# Sheet2.net
KiCad netlist of a schematic drawn in Altium Designer
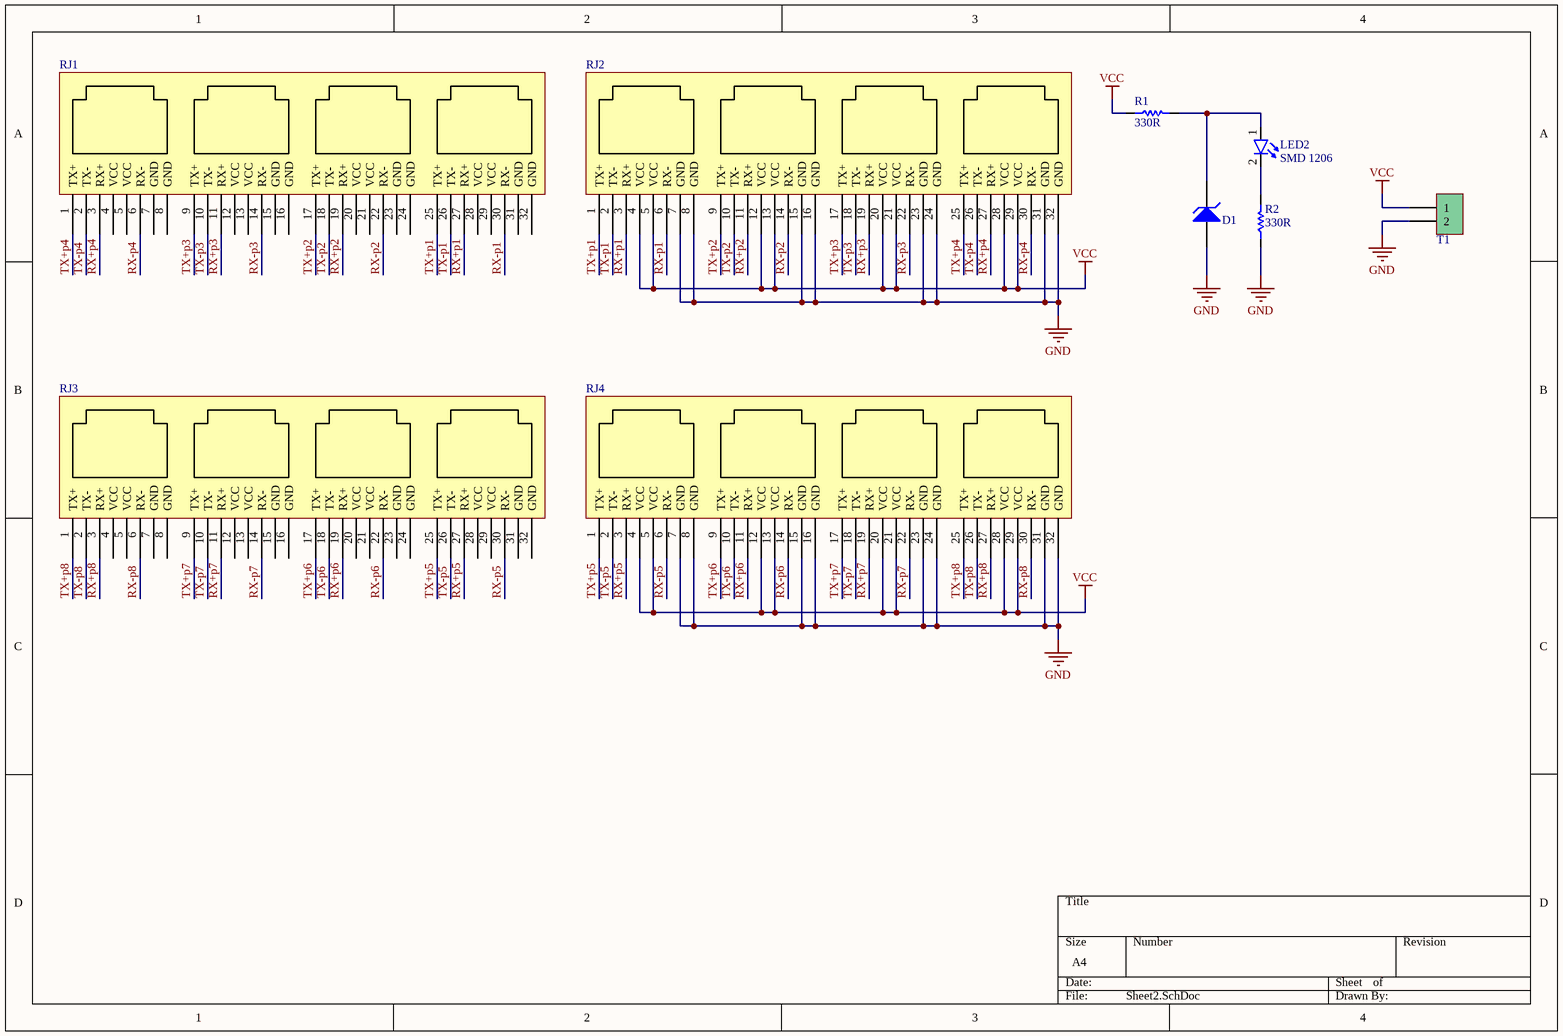
[diagram p0: Sheet2.SchDoc]

(export (version "E")
  (design (tool "Eeschema 10.0.6"))
  (components
    (comp (ref "D1")
      (value "Diode Zener")
      (footprint "Diode 1W")
      (description "Zener Diode")
      (fields (field (name "VOLTAGE") "12V") (field (name "DESIGNER") "Saeid Jorablo"))
      (libsource (lib "Electrovolt Lib") (part "Diode Zener"))
    )
    (comp (ref "LED2")
      (value "Red")
      (footprint "LED-5mm")
      (description "LED")
      (fields (field (name "SIZE") "SMD 1206") (field (name "DESIGNER") "Saeid Jorablo"))
      (libsource (lib "Electrovolt Lib") (part "LED"))
    )
    (comp (ref "R1")
      (value "330R")
      (footprint "RES 1206 (3216X08L)")
      (description "Resistor")
      (fields (field (name "TOLERANCE") "5%") (field (name "POWER") "1/8 W"))
      (libsource (lib "Electrovolt Lib") (part "Resistor"))
    )
    (comp (ref "R2")
      (value "330R")
      (footprint "RES 1206 (3216X08L)")
      (description "Resistor")
      (fields (field (name "TOLERANCE") "5%") (field (name "POWER") "1/8 W"))
      (libsource (lib "Electrovolt Lib") (part "Resistor"))
    )
    (comp (ref "RJ1") (value "~") (footprint "rj45-w57-4") (libsource (lib "Schlib1") (part "RJ45-w57-4")))
    (comp (ref "RJ2") (value "~") (footprint "rj45-w57-4") (libsource (lib "Schlib1") (part "RJ45-w57-4")))
    (comp (ref "RJ3") (value "~") (footprint "rj45-w57-4") (libsource (lib "Schlib1") (part "RJ45-w57-4")))
    (comp (ref "RJ4") (value "~") (footprint "rj45-w57-4") (libsource (lib "Schlib1") (part "RJ45-w57-4")))
    (comp (ref "T1")
      (value "Phoenix terminal")
      (footprint "phoenix terminal 2")
      (description "Terminal 2 Pin")
      (fields (field (name "DESIGNER") "Seyed Mohsen Ghasemain") (field (name "E-MAIL") "picpars@gmail.com"))
      (libsource (lib "usefully_Library") (part "Phoenix terminal 2"))
    )
  )
  (nets
    (net (code "1") (name "/RX+p1") (class "Default")
      (node (ref "RJ1") (pin "27") (pinfunction "RX+_27") (pintype "passive"))
      (node (ref "RJ2") (pin "3") (pinfunction "RX+_3") (pintype "passive"))
    )
    (net (code "2") (name "/RX+p2") (class "Default")
      (node (ref "RJ1") (pin "19") (pinfunction "RX+_19") (pintype "passive"))
      (node (ref "RJ2") (pin "11") (pinfunction "RX+_11") (pintype "passive"))
    )
    (net (code "3") (name "/RX+p3") (class "Default")
      (node (ref "RJ1") (pin "11") (pinfunction "RX+_11") (pintype "passive"))
      (node (ref "RJ2") (pin "19") (pinfunction "RX+_19") (pintype "passive"))
    )
    (net (code "4") (name "/RX+p4") (class "Default")
      (node (ref "RJ1") (pin "3") (pinfunction "RX+_3") (pintype "passive"))
      (node (ref "RJ2") (pin "27") (pinfunction "RX+_27") (pintype "passive"))
    )
    (net (code "5") (name "/RX+p5") (class "Default")
      (node (ref "RJ3") (pin "27") (pinfunction "RX+_27") (pintype "passive"))
      (node (ref "RJ4") (pin "3") (pinfunction "RX+_3") (pintype "passive"))
    )
    (net (code "6") (name "/RX+p6") (class "Default")
      (node (ref "RJ3") (pin "19") (pinfunction "RX+_19") (pintype "passive"))
      (node (ref "RJ4") (pin "11") (pinfunction "RX+_11") (pintype "passive"))
    )
    (net (code "7") (name "/RX+p7") (class "Default")
      (node (ref "RJ3") (pin "11") (pinfunction "RX+_11") (pintype "passive"))
      (node (ref "RJ4") (pin "19") (pinfunction "RX+_19") (pintype "passive"))
    )
    (net (code "8") (name "/RX+p8") (class "Default")
      (node (ref "RJ3") (pin "3") (pinfunction "RX+_3") (pintype "passive"))
      (node (ref "RJ4") (pin "27") (pinfunction "RX+_27") (pintype "passive"))
    )
    (net (code "9") (name "/RX-p1") (class "Default")
      (node (ref "RJ1") (pin "30") (pinfunction "RX-_30") (pintype "passive"))
      (node (ref "RJ2") (pin "6") (pinfunction "RX-_6") (pintype "passive"))
    )
    (net (code "10") (name "/RX-p2") (class "Default")
      (node (ref "RJ1") (pin "22") (pinfunction "RX-_22") (pintype "passive"))
      (node (ref "RJ2") (pin "14") (pinfunction "RX-_14") (pintype "passive"))
    )
    (net (code "11") (name "/RX-p3") (class "Default")
      (node (ref "RJ1") (pin "14") (pinfunction "RX-_14") (pintype "passive"))
      (node (ref "RJ2") (pin "22") (pinfunction "RX-_22") (pintype "passive"))
    )
    (net (code "12") (name "/RX-p4") (class "Default")
      (node (ref "RJ1") (pin "6") (pinfunction "RX-_6") (pintype "passive"))
      (node (ref "RJ2") (pin "30") (pinfunction "RX-_30") (pintype "passive"))
    )
    (net (code "13") (name "/RX-p5") (class "Default")
      (node (ref "RJ3") (pin "30") (pinfunction "RX-_30") (pintype "passive"))
      (node (ref "RJ4") (pin "6") (pinfunction "RX-_6") (pintype "passive"))
    )
    (net (code "14") (name "/RX-p6") (class "Default")
      (node (ref "RJ3") (pin "22") (pinfunction "RX-_22") (pintype "passive"))
      (node (ref "RJ4") (pin "14") (pinfunction "RX-_14") (pintype "passive"))
    )
    (net (code "15") (name "/RX-p7") (class "Default")
      (node (ref "RJ3") (pin "14") (pinfunction "RX-_14") (pintype "passive"))
      (node (ref "RJ4") (pin "22") (pinfunction "RX-_22") (pintype "passive"))
    )
    (net (code "16") (name "/RX-p8") (class "Default")
      (node (ref "RJ3") (pin "6") (pinfunction "RX-_6") (pintype "passive"))
      (node (ref "RJ4") (pin "30") (pinfunction "RX-_30") (pintype "passive"))
    )
    (net (code "17") (name "/TX+p1") (class "Default")
      (node (ref "RJ1") (pin "25") (pinfunction "TX+_25") (pintype "passive"))
      (node (ref "RJ2") (pin "1") (pinfunction "TX+_1") (pintype "passive"))
    )
    (net (code "18") (name "/TX+p2") (class "Default")
      (node (ref "RJ1") (pin "17") (pinfunction "TX+_17") (pintype "passive"))
      (node (ref "RJ2") (pin "9") (pinfunction "TX+_9") (pintype "passive"))
    )
    (net (code "19") (name "/TX+p3") (class "Default")
      (node (ref "RJ1") (pin "9") (pinfunction "TX+_9") (pintype "passive"))
      (node (ref "RJ2") (pin "17") (pinfunction "TX+_17") (pintype "passive"))
    )
    (net (code "20") (name "/TX+p4") (class "Default")
      (node (ref "RJ1") (pin "1") (pinfunction "TX+_1") (pintype "passive"))
      (node (ref "RJ2") (pin "25") (pinfunction "TX+_25") (pintype "passive"))
    )
    (net (code "21") (name "/TX+p5") (class "Default")
      (node (ref "RJ3") (pin "25") (pinfunction "TX+_25") (pintype "passive"))
      (node (ref "RJ4") (pin "1") (pinfunction "TX+_1") (pintype "passive"))
    )
    (net (code "22") (name "/TX+p6") (class "Default")
      (node (ref "RJ3") (pin "17") (pinfunction "TX+_17") (pintype "passive"))
      (node (ref "RJ4") (pin "9") (pinfunction "TX+_9") (pintype "passive"))
    )
    (net (code "23") (name "/TX+p7") (class "Default")
      (node (ref "RJ3") (pin "9") (pinfunction "TX+_9") (pintype "passive"))
      (node (ref "RJ4") (pin "17") (pinfunction "TX+_17") (pintype "passive"))
    )
    (net (code "24") (name "/TX+p8") (class "Default")
      (node (ref "RJ3") (pin "1") (pinfunction "TX+_1") (pintype "passive"))
      (node (ref "RJ4") (pin "25") (pinfunction "TX+_25") (pintype "passive"))
    )
    (net (code "25") (name "/TX-p1") (class "Default")
      (node (ref "RJ1") (pin "26") (pinfunction "TX-_26") (pintype "passive"))
      (node (ref "RJ2") (pin "2") (pinfunction "TX-_2") (pintype "passive"))
    )
    (net (code "26") (name "/TX-p2") (class "Default")
      (node (ref "RJ1") (pin "18") (pinfunction "TX-_18") (pintype "passive"))
      (node (ref "RJ2") (pin "10") (pinfunction "TX-_10") (pintype "passive"))
    )
    (net (code "27") (name "/TX-p3") (class "Default")
      (node (ref "RJ1") (pin "10") (pinfunction "TX-_10") (pintype "passive"))
      (node (ref "RJ2") (pin "18") (pinfunction "TX-_18") (pintype "passive"))
    )
    (net (code "28") (name "/TX-p4") (class "Default")
      (node (ref "RJ1") (pin "2") (pinfunction "TX-_2") (pintype "passive"))
      (node (ref "RJ2") (pin "26") (pinfunction "TX-_26") (pintype "passive"))
    )
    (net (code "29") (name "/TX-p5") (class "Default")
      (node (ref "RJ3") (pin "26") (pinfunction "TX-_26") (pintype "passive"))
      (node (ref "RJ4") (pin "2") (pinfunction "TX-_2") (pintype "passive"))
    )
    (net (code "30") (name "/TX-p6") (class "Default")
      (node (ref "RJ3") (pin "18") (pinfunction "TX-_18") (pintype "passive"))
      (node (ref "RJ4") (pin "10") (pinfunction "TX-_10") (pintype "passive"))
    )
    (net (code "31") (name "/TX-p7") (class "Default")
      (node (ref "RJ3") (pin "10") (pinfunction "TX-_10") (pintype "passive"))
      (node (ref "RJ4") (pin "18") (pinfunction "TX-_18") (pintype "passive"))
    )
    (net (code "32") (name "/TX-p8") (class "Default")
      (node (ref "RJ3") (pin "2") (pinfunction "TX-_2") (pintype "passive"))
      (node (ref "RJ4") (pin "26") (pinfunction "TX-_26") (pintype "passive"))
    )
    (net (code "33") (name "GND") (class "Default")
      (node (ref "D1") (pin "1") (pinfunction "A_1") (pintype "passive"))
      (node (ref "R2") (pin "1") (pinfunction "1_1") (pintype "passive"))
      (node (ref "RJ2") (pin "15") (pinfunction "GND_15") (pintype "passive"))
      (node (ref "RJ2") (pin "16") (pinfunction "GND_16") (pintype "passive"))
      (node (ref "RJ2") (pin "23") (pinfunction "GND_23") (pintype "passive"))
      (node (ref "RJ2") (pin "24") (pinfunction "GND_24") (pintype "passive"))
      (node (ref "RJ2") (pin "31") (pinfunction "GND_31") (pintype "passive"))
      (node (ref "RJ2") (pin "32") (pinfunction "GND_32") (pintype "passive"))
      (node (ref "RJ2") (pin "7") (pinfunction "GND_7") (pintype "passive"))
      (node (ref "RJ2") (pin "8") (pinfunction "GND_8") (pintype "passive"))
      (node (ref "RJ4") (pin "15") (pinfunction "GND_15") (pintype "passive"))
      (node (ref "RJ4") (pin "16") (pinfunction "GND_16") (pintype "passive"))
      (node (ref "RJ4") (pin "23") (pinfunction "GND_23") (pintype "passive"))
      (node (ref "RJ4") (pin "24") (pinfunction "GND_24") (pintype "passive"))
      (node (ref "RJ4") (pin "31") (pinfunction "GND_31") (pintype "passive"))
      (node (ref "RJ4") (pin "32") (pinfunction "GND_32") (pintype "passive"))
      (node (ref "RJ4") (pin "7") (pinfunction "GND_7") (pintype "passive"))
      (node (ref "RJ4") (pin "8") (pinfunction "GND_8") (pintype "passive"))
      (node (ref "T1") (pin "2") (pinfunction "2_2") (pintype "passive"))
    )
    (net (code "34") (name "Net-(D1-K)") (class "Default")
      (node (ref "D1") (pin "2") (pinfunction "K_2") (pintype "passive"))
      (node (ref "LED2") (pin "1") (pinfunction "A_1") (pintype "passive"))
      (node (ref "R1") (pin "2") (pinfunction "2_2") (pintype "passive"))
    )
    (net (code "35") (name "Net-(LED2-K)") (class "Default")
      (node (ref "LED2") (pin "2") (pinfunction "K_2") (pintype "passive"))
      (node (ref "R2") (pin "2") (pinfunction "2_2") (pintype "passive"))
    )
    (net (code "36") (name "VCC") (class "Default")
      (node (ref "R1") (pin "1") (pinfunction "1_1") (pintype "passive"))
      (node (ref "RJ2") (pin "12") (pinfunction "VCC_12") (pintype "passive"))
      (node (ref "RJ2") (pin "13") (pinfunction "VCC_13") (pintype "passive"))
      (node (ref "RJ2") (pin "20") (pinfunction "VCC_20") (pintype "passive"))
      (node (ref "RJ2") (pin "21") (pinfunction "VCC_21") (pintype "passive"))
      (node (ref "RJ2") (pin "28") (pinfunction "VCC_28") (pintype "passive"))
      (node (ref "RJ2") (pin "29") (pinfunction "VCC_29") (pintype "passive"))
      (node (ref "RJ2") (pin "4") (pinfunction "VCC_4") (pintype "passive"))
      (node (ref "RJ2") (pin "5") (pinfunction "VCC_5") (pintype "passive"))
      (node (ref "RJ4") (pin "12") (pinfunction "VCC_12") (pintype "passive"))
      (node (ref "RJ4") (pin "13") (pinfunction "VCC_13") (pintype "passive"))
      (node (ref "RJ4") (pin "20") (pinfunction "VCC_20") (pintype "passive"))
      (node (ref "RJ4") (pin "21") (pinfunction "VCC_21") (pintype "passive"))
      (node (ref "RJ4") (pin "28") (pinfunction "VCC_28") (pintype "passive"))
      (node (ref "RJ4") (pin "29") (pinfunction "VCC_29") (pintype "passive"))
      (node (ref "RJ4") (pin "4") (pinfunction "VCC_4") (pintype "passive"))
      (node (ref "RJ4") (pin "5") (pinfunction "VCC_5") (pintype "passive"))
      (node (ref "T1") (pin "1") (pinfunction "1_1") (pintype "passive"))
    )
    (net (code "37") (name "unconnected-(RJ1-GND-Pad7)") (class "Default")
      (node (ref "RJ1") (pin "7") (pinfunction "GND_7") (pintype "passive"))
    )
    (net (code "38") (name "unconnected-(RJ1-GND-Pad8)") (class "Default")
      (node (ref "RJ1") (pin "8") (pinfunction "GND_8") (pintype "passive"))
    )
    (net (code "39") (name "unconnected-(RJ1-GND-Pad15)") (class "Default")
      (node (ref "RJ1") (pin "15") (pinfunction "GND_15") (pintype "passive"))
    )
    (net (code "40") (name "unconnected-(RJ1-GND-Pad16)") (class "Default")
      (node (ref "RJ1") (pin "16") (pinfunction "GND_16") (pintype "passive"))
    )
    (net (code "41") (name "unconnected-(RJ1-GND-Pad23)") (class "Default")
      (node (ref "RJ1") (pin "23") (pinfunction "GND_23") (pintype "passive"))
    )
    (net (code "42") (name "unconnected-(RJ1-GND-Pad24)") (class "Default")
      (node (ref "RJ1") (pin "24") (pinfunction "GND_24") (pintype "passive"))
    )
    (net (code "43") (name "unconnected-(RJ1-GND-Pad31)") (class "Default")
      (node (ref "RJ1") (pin "31") (pinfunction "GND_31") (pintype "passive"))
    )
    (net (code "44") (name "unconnected-(RJ1-GND-Pad32)") (class "Default")
      (node (ref "RJ1") (pin "32") (pinfunction "GND_32") (pintype "passive"))
    )
    (net (code "45") (name "unconnected-(RJ1-VCC-Pad4)") (class "Default")
      (node (ref "RJ1") (pin "4") (pinfunction "VCC_4") (pintype "passive"))
    )
    (net (code "46") (name "unconnected-(RJ1-VCC-Pad5)") (class "Default")
      (node (ref "RJ1") (pin "5") (pinfunction "VCC_5") (pintype "passive"))
    )
    (net (code "47") (name "unconnected-(RJ1-VCC-Pad12)") (class "Default")
      (node (ref "RJ1") (pin "12") (pinfunction "VCC_12") (pintype "passive"))
    )
    (net (code "48") (name "unconnected-(RJ1-VCC-Pad13)") (class "Default")
      (node (ref "RJ1") (pin "13") (pinfunction "VCC_13") (pintype "passive"))
    )
    (net (code "49") (name "unconnected-(RJ1-VCC-Pad20)") (class "Default")
      (node (ref "RJ1") (pin "20") (pinfunction "VCC_20") (pintype "passive"))
    )
    (net (code "50") (name "unconnected-(RJ1-VCC-Pad21)") (class "Default")
      (node (ref "RJ1") (pin "21") (pinfunction "VCC_21") (pintype "passive"))
    )
    (net (code "51") (name "unconnected-(RJ1-VCC-Pad28)") (class "Default")
      (node (ref "RJ1") (pin "28") (pinfunction "VCC_28") (pintype "passive"))
    )
    (net (code "52") (name "unconnected-(RJ1-VCC-Pad29)") (class "Default")
      (node (ref "RJ1") (pin "29") (pinfunction "VCC_29") (pintype "passive"))
    )
    (net (code "53") (name "unconnected-(RJ3-GND-Pad7)") (class "Default")
      (node (ref "RJ3") (pin "7") (pinfunction "GND_7") (pintype "passive"))
    )
    (net (code "54") (name "unconnected-(RJ3-GND-Pad8)") (class "Default")
      (node (ref "RJ3") (pin "8") (pinfunction "GND_8") (pintype "passive"))
    )
    (net (code "55") (name "unconnected-(RJ3-GND-Pad15)") (class "Default")
      (node (ref "RJ3") (pin "15") (pinfunction "GND_15") (pintype "passive"))
    )
    (net (code "56") (name "unconnected-(RJ3-GND-Pad16)") (class "Default")
      (node (ref "RJ3") (pin "16") (pinfunction "GND_16") (pintype "passive"))
    )
    (net (code "57") (name "unconnected-(RJ3-GND-Pad23)") (class "Default")
      (node (ref "RJ3") (pin "23") (pinfunction "GND_23") (pintype "passive"))
    )
    (net (code "58") (name "unconnected-(RJ3-GND-Pad24)") (class "Default")
      (node (ref "RJ3") (pin "24") (pinfunction "GND_24") (pintype "passive"))
    )
    (net (code "59") (name "unconnected-(RJ3-GND-Pad31)") (class "Default")
      (node (ref "RJ3") (pin "31") (pinfunction "GND_31") (pintype "passive"))
    )
    (net (code "60") (name "unconnected-(RJ3-GND-Pad32)") (class "Default")
      (node (ref "RJ3") (pin "32") (pinfunction "GND_32") (pintype "passive"))
    )
    (net (code "61") (name "unconnected-(RJ3-VCC-Pad4)") (class "Default")
      (node (ref "RJ3") (pin "4") (pinfunction "VCC_4") (pintype "passive"))
    )
    (net (code "62") (name "unconnected-(RJ3-VCC-Pad5)") (class "Default")
      (node (ref "RJ3") (pin "5") (pinfunction "VCC_5") (pintype "passive"))
    )
    (net (code "63") (name "unconnected-(RJ3-VCC-Pad12)") (class "Default")
      (node (ref "RJ3") (pin "12") (pinfunction "VCC_12") (pintype "passive"))
    )
    (net (code "64") (name "unconnected-(RJ3-VCC-Pad13)") (class "Default")
      (node (ref "RJ3") (pin "13") (pinfunction "VCC_13") (pintype "passive"))
    )
    (net (code "65") (name "unconnected-(RJ3-VCC-Pad20)") (class "Default")
      (node (ref "RJ3") (pin "20") (pinfunction "VCC_20") (pintype "passive"))
    )
    (net (code "66") (name "unconnected-(RJ3-VCC-Pad21)") (class "Default")
      (node (ref "RJ3") (pin "21") (pinfunction "VCC_21") (pintype "passive"))
    )
    (net (code "67") (name "unconnected-(RJ3-VCC-Pad28)") (class "Default")
      (node (ref "RJ3") (pin "28") (pinfunction "VCC_28") (pintype "passive"))
    )
    (net (code "68") (name "unconnected-(RJ3-VCC-Pad29)") (class "Default")
      (node (ref "RJ3") (pin "29") (pinfunction "VCC_29") (pintype "passive"))
    )
  )
)
